# Sheet1.net
KiCad netlist of a schematic drawn in Altium Designer
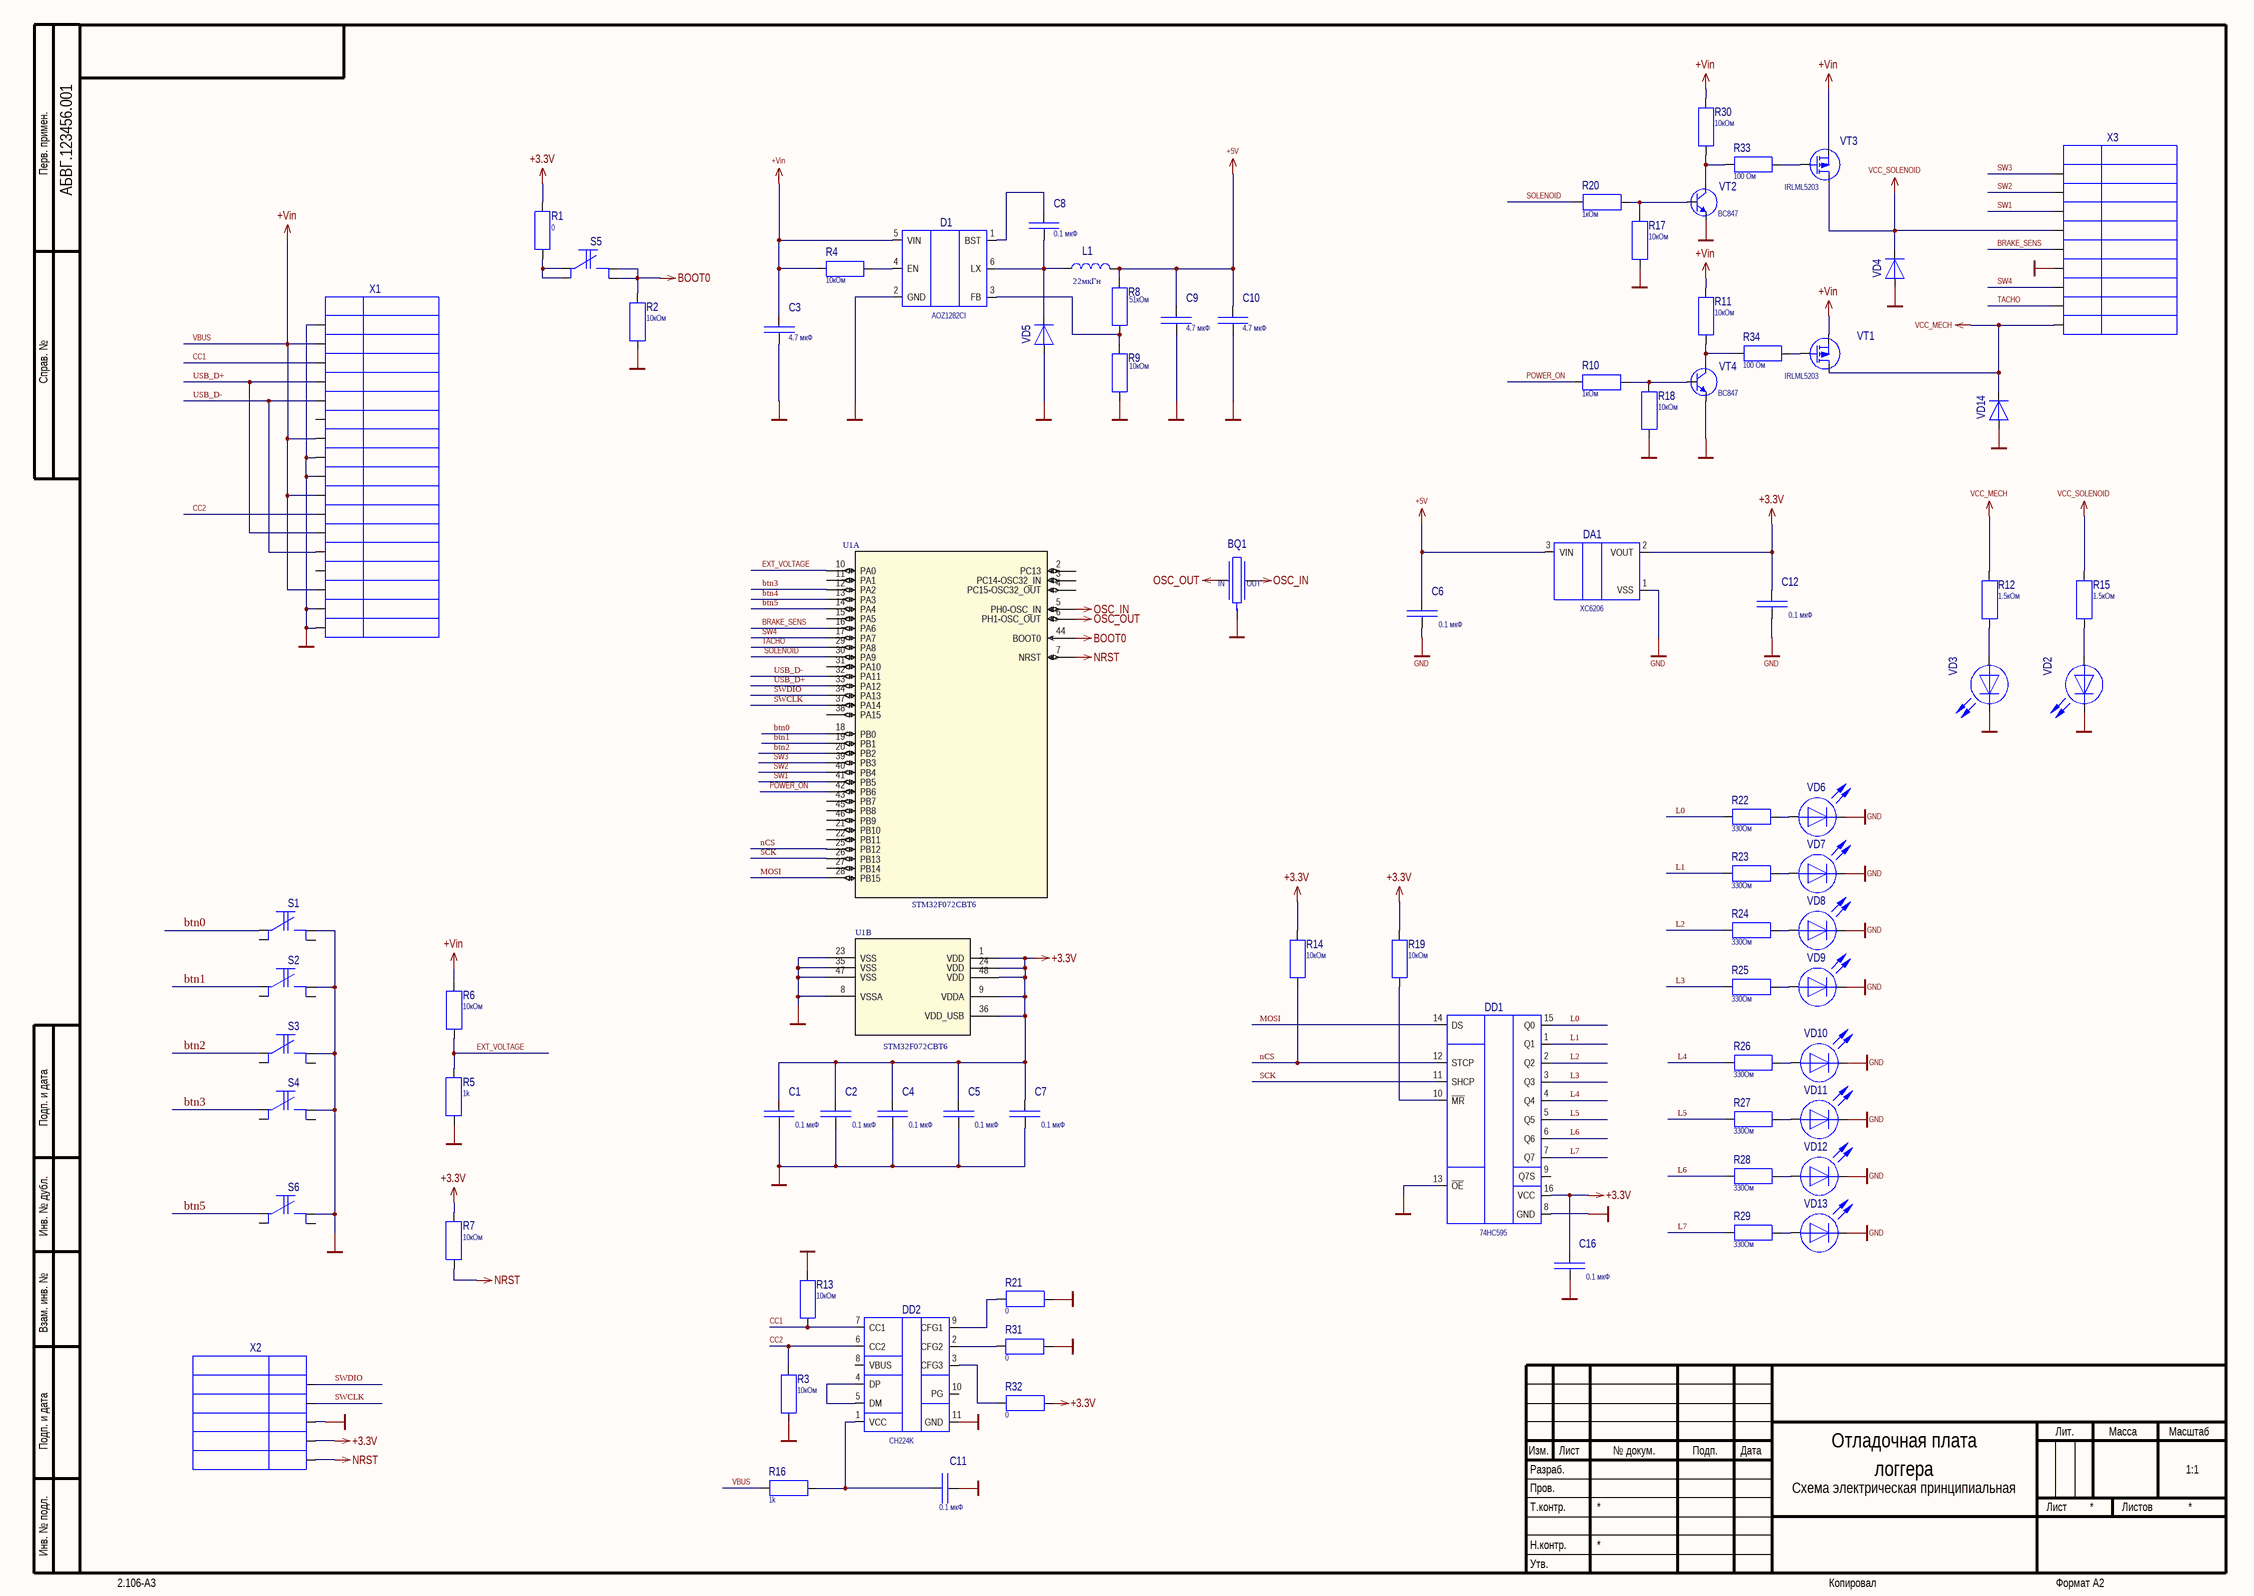
[diagram p0: Sheet1.SchDoc]

(export (version "E")
  (design (tool "Eeschema 10.0.6"))
  (components
    (comp (ref "BQ1")
      (value "CSTCE8M00G15C99")
      (footprint "CRYSTAL-SMD_3P-L3.2-W1.3-P1.2-BL-1")
      (fields (field (name "MANUFACTURER") "ф. Murata"))
      (libsource (lib "Common_lib") (part "CSTCE8M00G15C99"))
    )
    (comp (ref "C1")
      (value "0.1 мкФ")
      (footprint "C0805")
      (fields (field (name "TOLERANCE") "5%") (field (name "Comment") "C_2"))
      (libsource (lib "tsb_lib") (part "C_2"))
    )
    (comp (ref "C2")
      (value "0.1 мкФ")
      (footprint "C0805")
      (fields (field (name "TOLERANCE") "5%") (field (name "Comment") "C_2"))
      (libsource (lib "tsb_lib") (part "C_2"))
    )
    (comp (ref "C3")
      (value "4.7 мкФ")
      (footprint "C0805")
      (fields (field (name "TOLERANCE") "5%") (field (name "Comment") "C_2"))
      (libsource (lib "tsb_lib") (part "C_2"))
    )
    (comp (ref "C4")
      (value "0.1 мкФ")
      (footprint "C0805")
      (fields (field (name "TOLERANCE") "5%") (field (name "Comment") "C_2"))
      (libsource (lib "tsb_lib") (part "C_2"))
    )
    (comp (ref "C5")
      (value "0.1 мкФ")
      (footprint "C0805")
      (fields (field (name "TOLERANCE") "5%") (field (name "Comment") "C_2"))
      (libsource (lib "tsb_lib") (part "C_2"))
    )
    (comp (ref "C6")
      (value "0.1 мкФ")
      (footprint "C0805")
      (fields (field (name "TOLERANCE") "5%") (field (name "Comment") "C_2"))
      (libsource (lib "tsb_lib") (part "C_2"))
    )
    (comp (ref "C7")
      (value "0.1 мкФ")
      (footprint "C0805")
      (fields (field (name "TOLERANCE") "5%") (field (name "Comment") "C_2"))
      (libsource (lib "tsb_lib") (part "C_2"))
    )
    (comp (ref "C8")
      (value "0.1 мкФ")
      (footprint "C0805")
      (fields (field (name "TOLERANCE") "5%") (field (name "Comment") "C_2"))
      (libsource (lib "tsb_lib") (part "C_2"))
    )
    (comp (ref "C9")
      (value "4.7 мкФ")
      (footprint "C0805")
      (fields (field (name "TOLERANCE") "5%") (field (name "Comment") "C_2"))
      (libsource (lib "tsb_lib") (part "C_2"))
    )
    (comp (ref "C10")
      (value "4.7 мкФ")
      (footprint "C0805")
      (fields (field (name "TOLERANCE") "5%") (field (name "Comment") "C_2"))
      (libsource (lib "tsb_lib") (part "C_2"))
    )
    (comp (ref "C11")
      (value "0.1 мкФ")
      (footprint "C0805")
      (fields (field (name "TOLERANCE") "5%") (field (name "Comment") "C_2"))
      (libsource (lib "tsb_lib") (part "C_2"))
    )
    (comp (ref "C12")
      (value "0.1 мкФ")
      (footprint "C0805")
      (fields (field (name "TOLERANCE") "5%") (field (name "Comment") "C_2"))
      (libsource (lib "tsb_lib") (part "C_2"))
    )
    (comp (ref "C16")
      (value "0.1 мкФ")
      (footprint "C0805")
      (fields (field (name "TOLERANCE") "5%") (field (name "Comment") "C_2"))
      (libsource (lib "tsb_lib") (part "C_2"))
    )
    (comp (ref "D1")
      (value "AOZ1282CI")
      (footprint "SOT23-6_M")
      (fields (field (name "MANUFACTURER") "ф. Alpha & Omega"))
      (libsource (lib "Common_lib") (part "AOZ1282CI"))
    )
    (comp (ref "DA1")
      (value "XC6206")
      (footprint "SOT23_S")
      (fields (field (name "MANUFACTURER") "ф. Torex"))
      (libsource (lib "Common_lib") (part "XC6206"))
    )
    (comp (ref "DD1")
      (value "74HC595")
      (footprint "SO-16_M")
      (fields
        (field (name "MANUFACTURER") "ф. Nexperia B.V.")
        (field (name "MANUFACTURERPARTNUMBER") "74HC595D")
      )
      (libsource (lib "Common_lib") (part "74HC595"))
    )
    (comp (ref "DD2")
      (value "CH224K")
      (footprint "ESSOP-10_L4.9-W3.9-P1.0-LS6.0-TL-EP")
      (fields (field (name "MANUFACTURER") "ф. WCH"))
      (libsource (lib "Common_lib") (part "CH224K"))
    )
    (comp (ref "L1")
      (value "22мкГн")
      (footprint "4.5X3.0")
      (fields
        (field (name "MANUFACTURER") "ф. CODACA")
        (field (name "TOLERANCE") "10%")
        (field (name "Comment") "L_1")
      )
      (libsource (lib "Common_lib") (part "L_1"))
    )
    (comp (ref "R1")
      (value "0")
      (footprint "r0805")
      (fields (field (name "TOLERANCE") "5%") (field (name "Comment") "R_1"))
      (libsource (lib "rc_lib") (part "R_1"))
    )
    (comp (ref "R2")
      (value "10кОм")
      (footprint "r0805")
      (fields (field (name "TOLERANCE") "5%") (field (name "Comment") "R_1"))
      (libsource (lib "rc_lib") (part "R_1"))
    )
    (comp (ref "R3")
      (value "10кОм")
      (footprint "r0805")
      (fields (field (name "TOLERANCE") "5%") (field (name "Comment") "R_1"))
      (libsource (lib "rc_lib") (part "R_1"))
    )
    (comp (ref "R4")
      (value "10кОм")
      (footprint "R0805")
      (fields (field (name "TOLERANCE") "5%") (field (name "Comment") "R_1"))
      (libsource (lib "rc_lib") (part "R_1"))
    )
    (comp (ref "R5")
      (value "1k")
      (footprint "r0805")
      (fields (field (name "TOLERANCE") "5%") (field (name "Comment") "R_1"))
      (libsource (lib "rc_lib") (part "R_1"))
    )
    (comp (ref "R6")
      (value "10кОм")
      (footprint "r0805")
      (fields (field (name "TOLERANCE") "5%") (field (name "Comment") "R_1"))
      (libsource (lib "rc_lib") (part "R_1"))
    )
    (comp (ref "R7")
      (value "10кОм")
      (footprint "r0805")
      (fields (field (name "TOLERANCE") "5%") (field (name "Comment") "R_1"))
      (libsource (lib "rc_lib") (part "R_1"))
    )
    (comp (ref "R8")
      (value "51кОм")
      (footprint "R0805")
      (fields (field (name "TOLERANCE") "5%") (field (name "Comment") "R_1"))
      (libsource (lib "rc_lib") (part "R_1"))
    )
    (comp (ref "R9")
      (value "10кОм")
      (footprint "R0805")
      (fields (field (name "TOLERANCE") "5%") (field (name "Comment") "R_1"))
      (libsource (lib "rc_lib") (part "R_1"))
    )
    (comp (ref "R10")
      (value "1кОм")
      (footprint "r0805")
      (fields (field (name "TOLERANCE") "5%") (field (name "Comment") "R_1"))
      (libsource (lib "rc_lib") (part "R_1"))
    )
    (comp (ref "R11")
      (value "10кОм")
      (footprint "r0805")
      (fields (field (name "TOLERANCE") "5%") (field (name "Comment") "R_1"))
      (libsource (lib "rc_lib") (part "R_1"))
    )
    (comp (ref "R12")
      (value "1.5кОм")
      (footprint "R0805")
      (fields (field (name "TOLERANCE") "5%") (field (name "Comment") "R_1"))
      (libsource (lib "rc_lib") (part "R_1"))
    )
    (comp (ref "R13")
      (value "10кОм")
      (footprint "r0805")
      (fields (field (name "TOLERANCE") "5%") (field (name "Comment") "R_1"))
      (libsource (lib "rc_lib") (part "R_1"))
    )
    (comp (ref "R14")
      (value "10кОм")
      (footprint "r0805")
      (fields (field (name "TOLERANCE") "5%") (field (name "Comment") "R_1"))
      (libsource (lib "rc_lib") (part "R_1"))
    )
    (comp (ref "R15")
      (value "1.5кОм")
      (footprint "R0805")
      (fields (field (name "TOLERANCE") "5%") (field (name "Comment") "R_1"))
      (libsource (lib "rc_lib") (part "R_1"))
    )
    (comp (ref "R16")
      (value "1k")
      (footprint "r0805")
      (fields (field (name "TOLERANCE") "5%") (field (name "Comment") "R_1"))
      (libsource (lib "rc_lib") (part "R_1"))
    )
    (comp (ref "R17")
      (value "10кОм")
      (footprint "r0805")
      (fields (field (name "TOLERANCE") "5%") (field (name "Comment") "R_1"))
      (libsource (lib "rc_lib") (part "R_1"))
    )
    (comp (ref "R18")
      (value "10кОм")
      (footprint "r0805")
      (fields (field (name "TOLERANCE") "5%") (field (name "Comment") "R_1"))
      (libsource (lib "rc_lib") (part "R_1"))
    )
    (comp (ref "R19")
      (value "10кОм")
      (footprint "r0805")
      (fields (field (name "TOLERANCE") "5%") (field (name "Comment") "R_1"))
      (libsource (lib "rc_lib") (part "R_1"))
    )
    (comp (ref "R20")
      (value "1кОм")
      (footprint "r0805")
      (fields (field (name "TOLERANCE") "5%") (field (name "Comment") "R_1"))
      (libsource (lib "rc_lib") (part "R_1"))
    )
    (comp (ref "R21")
      (value "0")
      (footprint "r0805")
      (fields (field (name "TOLERANCE") "5%") (field (name "Comment") "R_1"))
      (libsource (lib "rc_lib") (part "R_1"))
    )
    (comp (ref "R22")
      (value "330Ом")
      (footprint "R0805")
      (fields (field (name "TOLERANCE") "5%") (field (name "Comment") "R_1"))
      (libsource (lib "rc_lib") (part "R_1"))
    )
    (comp (ref "R23")
      (value "330Ом")
      (footprint "R0805")
      (fields (field (name "TOLERANCE") "5%") (field (name "Comment") "R_1"))
      (libsource (lib "rc_lib") (part "R_1"))
    )
    (comp (ref "R24")
      (value "330Ом")
      (footprint "R0805")
      (fields (field (name "TOLERANCE") "5%") (field (name "Comment") "R_1"))
      (libsource (lib "rc_lib") (part "R_1"))
    )
    (comp (ref "R25")
      (value "330Ом")
      (footprint "R0805")
      (fields (field (name "TOLERANCE") "5%") (field (name "Comment") "R_1"))
      (libsource (lib "rc_lib") (part "R_1"))
    )
    (comp (ref "R26")
      (value "330Ом")
      (footprint "R0805")
      (fields (field (name "TOLERANCE") "5%") (field (name "Comment") "R_1"))
      (libsource (lib "rc_lib") (part "R_1"))
    )
    (comp (ref "R27")
      (value "330Ом")
      (footprint "R0805")
      (fields (field (name "TOLERANCE") "5%") (field (name "Comment") "R_1"))
      (libsource (lib "rc_lib") (part "R_1"))
    )
    (comp (ref "R28")
      (value "330Ом")
      (footprint "R0805")
      (fields (field (name "TOLERANCE") "5%") (field (name "Comment") "R_1"))
      (libsource (lib "rc_lib") (part "R_1"))
    )
    (comp (ref "R29")
      (value "330Ом")
      (footprint "R0805")
      (fields (field (name "TOLERANCE") "5%") (field (name "Comment") "R_1"))
      (libsource (lib "rc_lib") (part "R_1"))
    )
    (comp (ref "R30")
      (value "10кОм")
      (footprint "r0805")
      (fields (field (name "TOLERANCE") "5%") (field (name "Comment") "R_1"))
      (libsource (lib "rc_lib") (part "R_1"))
    )
    (comp (ref "R31")
      (value "0")
      (footprint "r0805")
      (fields (field (name "TOLERANCE") "5%") (field (name "Comment") "R_1"))
      (libsource (lib "rc_lib") (part "R_1"))
    )
    (comp (ref "R32")
      (value "0")
      (footprint "r0805")
      (fields (field (name "TOLERANCE") "5%") (field (name "Comment") "R_1"))
      (libsource (lib "rc_lib") (part "R_1"))
    )
    (comp (ref "R33")
      (value "100 Ом")
      (footprint "r0805")
      (fields (field (name "TOLERANCE") "5%") (field (name "Comment") "R_1"))
      (libsource (lib "rc_lib") (part "R_1"))
    )
    (comp (ref "R34")
      (value "100 Ом")
      (footprint "r0805")
      (fields (field (name "TOLERANCE") "5%") (field (name "Comment") "R_1"))
      (libsource (lib "rc_lib") (part "R_1"))
    )
    (comp (ref "S1")
      (value "SW_BOT")
      (footprint "SW-PB")
      (fields (field (name "MANUFACTURERPARTNUMBER") "Кнопка тактовая 4.5x6.5мм"))
      (libsource (lib "Common_lib") (part "SW_BOT"))
    )
    (comp (ref "S2")
      (value "SW_BOT")
      (footprint "SW-PB")
      (fields (field (name "MANUFACTURERPARTNUMBER") "Кнопка тактовая 4.5x6.5мм"))
      (libsource (lib "Common_lib") (part "SW_BOT"))
    )
    (comp (ref "S3")
      (value "SW_BOT")
      (footprint "SW-PB")
      (fields (field (name "MANUFACTURERPARTNUMBER") "Кнопка тактовая 4.5x6.5мм"))
      (libsource (lib "Common_lib") (part "SW_BOT"))
    )
    (comp (ref "S4")
      (value "SW_BOT")
      (footprint "SW-PB")
      (fields (field (name "MANUFACTURERPARTNUMBER") "Кнопка тактовая 4.5x6.5мм"))
      (libsource (lib "Common_lib") (part "SW_BOT"))
    )
    (comp (ref "S5")
      (value "SW_BOT")
      (footprint "SW-PB")
      (fields (field (name "MANUFACTURERPARTNUMBER") "Кнопка тактовая 4.5x6.5мм"))
      (libsource (lib "Common_lib") (part "SW_BOT"))
    )
    (comp (ref "S6")
      (value "SW_BOT")
      (footprint "SW-PB")
      (fields (field (name "MANUFACTURERPARTNUMBER") "Кнопка тактовая 4.5x6.5мм"))
      (libsource (lib "Common_lib") (part "SW_BOT"))
    )
    (comp (ref "U1")
      (value "STM32F072CBT6")
      (footprint "TQFP48_M")
      (description "No Description Available")
      (fields
        (field (name "MANUFACTURER_PART_NUMBER") "stm32l052cl3")
        (field (name "COPYRIGHT") "Copyright (C) 2016 Accelerated Designs. All rights reserved")
      )
      (libsource (lib "2019-10-06_14-30-46") (part "STM32L052CL3"))
    )
    (comp (ref "VD2")
      (value "LED")
      (footprint "L0805")
      (fields (field (name "MANUFACTURERPARTNUMBER") "KPT-2012SGC (Красный)  *любой 0805"))
      (libsource (lib "rc_lib") (part "LED"))
    )
    (comp (ref "VD3")
      (value "LED")
      (footprint "L0805")
      (fields (field (name "MANUFACTURERPARTNUMBER") "KPT-2012SGC (Красный)  *любой 0805"))
      (libsource (lib "rc_lib") (part "LED"))
    )
    (comp (ref "VD4")
      (value "MBR0540T1G")
      (footprint "SOD123")
      (fields (field (name "MANUFACTURER") "ф.  ON Semi"))
      (libsource (lib "log_lib") (part "MBR0540T1G"))
    )
    (comp (ref "VD5")
      (value "MBR0540T1G")
      (footprint "SOD123")
      (fields (field (name "MANUFACTURER") "ф.  ON Semi"))
      (libsource (lib "log_lib") (part "MBR0540T1G"))
    )
    (comp (ref "VD6")
      (value "LED")
      (footprint "L0805")
      (fields (field (name "MANUFACTURERPARTNUMBER") "KPT-2012SGC (Зеленый)  *любой 0805"))
      (libsource (lib "rc_lib") (part "LED"))
    )
    (comp (ref "VD7")
      (value "LED")
      (footprint "L0805")
      (fields (field (name "MANUFACTURERPARTNUMBER") "KPT-2012SGC (Зеленый)  *любой 0805"))
      (libsource (lib "rc_lib") (part "LED"))
    )
    (comp (ref "VD8")
      (value "LED")
      (footprint "L0805")
      (fields (field (name "MANUFACTURERPARTNUMBER") "KPT-2012SGC (Зеленый)  *любой 0805"))
      (libsource (lib "rc_lib") (part "LED"))
    )
    (comp (ref "VD9")
      (value "LED")
      (footprint "L0805")
      (fields (field (name "MANUFACTURERPARTNUMBER") "KPT-2012SGC (Зеленый)  *любой 0805"))
      (libsource (lib "rc_lib") (part "LED"))
    )
    (comp (ref "VD10")
      (value "LED")
      (footprint "L0805")
      (fields (field (name "MANUFACTURERPARTNUMBER") "KPT-2012SGC (Зеленый)  *любой 0805"))
      (libsource (lib "rc_lib") (part "LED"))
    )
    (comp (ref "VD11")
      (value "LED")
      (footprint "L0805")
      (fields (field (name "MANUFACTURERPARTNUMBER") "KPT-2012SGC (Зеленый)  *любой 0805"))
      (libsource (lib "rc_lib") (part "LED"))
    )
    (comp (ref "VD12")
      (value "LED")
      (footprint "L0805")
      (fields (field (name "MANUFACTURERPARTNUMBER") "KPT-2012SGC (Зеленый)  *любой 0805"))
      (libsource (lib "rc_lib") (part "LED"))
    )
    (comp (ref "VD13")
      (value "LED")
      (footprint "L0805")
      (fields (field (name "MANUFACTURERPARTNUMBER") "KPT-2012SGC (Зеленый)  *любой 0805"))
      (libsource (lib "rc_lib") (part "LED"))
    )
    (comp (ref "VD14")
      (value "MBR0540T1G")
      (footprint "SOD123")
      (fields (field (name "MANUFACTURER") "ф.  ON Semi"))
      (libsource (lib "log_lib") (part "MBR0540T1G"))
    )
    (comp (ref "VT1")
      (value "IRLML5203")
      (footprint "SOT23_M")
      (fields (field (name "MANUFACTURER") "ф. IR"))
      (libsource (lib "Common_lib") (part "IRLML5203"))
    )
    (comp (ref "VT2")
      (value "BC847")
      (footprint "SOT23_S")
      (fields (field (name "MANUFACTURER") "ф. NXP"))
      (libsource (lib "Common_lib") (part "BC847"))
    )
    (comp (ref "VT3")
      (value "IRLML5203")
      (footprint "SOT23_M")
      (fields (field (name "MANUFACTURER") "ф. IR"))
      (libsource (lib "Common_lib") (part "IRLML5203"))
    )
    (comp (ref "VT4")
      (value "BC847")
      (footprint "SOT23_S")
      (fields (field (name "MANUFACTURER") "ф. NXP"))
      (libsource (lib "Common_lib") (part "BC847"))
    )
    (comp (ref "X1")
      (value "USBC-16PIN-VERTICAL")
      (footprint "USB-C-16-pin-vertical")
      (fields
        (field (name "MANUFACTURER") "ф. Ningbo Zhenqin Electronic")
        (field (name "MANUFACTURERPARTNUMBER") "PLS11")
      )
      (libsource (lib "Common_lib") (part "USBC-16PIN-VERTICAL"))
    )
    (comp (ref "X2")
      (value "PLS5")
      (footprint "HDR1X5")
      (fields (field (name "MANUFACTURER") "ф. Ningbo Zhenqin Electronic"))
      (libsource (lib "Common_lib") (part "PLS5"))
    )
    (comp (ref "X3")
      (value "PLS9")
      (footprint "PH-9A_P")
      (fields
        (field (name "MANUFACTURER") "ф. Ningbo Zhenqin Electronic")
        (field (name "MANUFACTURERPARTNUMBER") "PH2.0-9A_P")
      )
      (libsource (lib "Common_lib") (part "PLS9"))
    )
  )
  (nets
    (net (code "1") (name "+3.3V") (class "Default")
      (node (ref "C1") (pin "1") (pintype "passive"))
      (node (ref "C12") (pin "1") (pintype "passive"))
      (node (ref "C16") (pin "1") (pintype "passive"))
      (node (ref "C2") (pin "1") (pintype "passive"))
      (node (ref "C4") (pin "1") (pintype "passive"))
      (node (ref "C5") (pin "1") (pintype "passive"))
      (node (ref "C7") (pin "1") (pintype "passive"))
      (node (ref "DA1") (pin "2") (pinfunction "VOUT_2") (pintype "passive"))
      (node (ref "DD1") (pin "16") (pinfunction "VCC_16") (pintype "passive"))
      (node (ref "R1") (pin "2") (pintype "passive"))
      (node (ref "R14") (pin "1") (pintype "passive"))
      (node (ref "R19") (pin "1") (pintype "passive"))
      (node (ref "R32") (pin "1") (pintype "passive"))
      (node (ref "R7") (pin "2") (pintype "passive"))
      (node (ref "U1") (pin "1") (pinfunction "VDD_1") (pintype "power_in"))
      (node (ref "U1") (pin "24") (pinfunction "VDD_24") (pintype "power_in"))
      (node (ref "U1") (pin "36") (pinfunction "VDD_USB_36") (pintype "power_in"))
      (node (ref "U1") (pin "48") (pinfunction "VDD_48") (pintype "power_in"))
      (node (ref "U1") (pin "9") (pinfunction "VDDA_9") (pintype "power_in"))
      (node (ref "X2") (pin "4") (pintype "passive"))
    )
    (net (code "2") (name "+5V") (class "Default")
      (node (ref "C10") (pin "1") (pintype "passive"))
      (node (ref "C6") (pin "1") (pintype "passive"))
      (node (ref "C9") (pin "1") (pintype "passive"))
      (node (ref "DA1") (pin "3") (pinfunction "VIN_3") (pintype "passive"))
      (node (ref "L1") (pin "2") (pintype "passive"))
      (node (ref "R8") (pin "1") (pintype "passive"))
    )
    (net (code "3") (name "+Vin") (class "Default")
      (node (ref "C3") (pin "1") (pintype "passive"))
      (node (ref "D1") (pin "5") (pinfunction "VIN_5") (pintype "passive"))
      (node (ref "R11") (pin "1") (pintype "passive"))
      (node (ref "R16") (pin "2") (pintype "passive"))
      (node (ref "R30") (pin "1") (pintype "passive"))
      (node (ref "R4") (pin "1") (pintype "passive"))
      (node (ref "R6") (pin "1") (pintype "passive"))
      (node (ref "VT1") (pin "2") (pinfunction "S_2") (pintype "passive"))
      (node (ref "VT3") (pin "2") (pinfunction "S_2") (pintype "passive"))
      (node (ref "X1") (pin "A4") (pintype "passive"))
      (node (ref "X1") (pin "A9") (pintype "passive"))
      (node (ref "X1") (pin "B4") (pintype "passive"))
      (node (ref "X1") (pin "B9") (pintype "passive"))
    )
    (net (code "4") (name "/BRAKE_SENS") (class "Default")
      (node (ref "U1") (pin "16") (pinfunction "PA6_16") (pintype "bidirectional"))
      (node (ref "X3") (pin "5") (pintype "passive"))
    )
    (net (code "5") (name "/CC1") (class "Default")
      (node (ref "DD2") (pin "7") (pinfunction "CC1_7") (pintype "passive"))
      (node (ref "R13") (pin "2") (pintype "passive"))
      (node (ref "X1") (pin "A5") (pintype "passive"))
    )
    (net (code "6") (name "/CC2") (class "Default")
      (node (ref "DD2") (pin "6") (pinfunction "CC2_6") (pintype "passive"))
      (node (ref "R3") (pin "1") (pintype "passive"))
      (node (ref "X1") (pin "B5") (pintype "passive"))
    )
    (net (code "7") (name "/EXT_VOLTAGE") (class "Default")
      (node (ref "R5") (pin "2") (pintype "passive"))
      (node (ref "R6") (pin "2") (pintype "passive"))
      (node (ref "U1") (pin "10") (pinfunction "PA0_10") (pintype "bidirectional"))
    )
    (net (code "8") (name "/L0") (class "Default")
      (node (ref "DD1") (pin "15") (pinfunction "Q0_15") (pintype "passive"))
      (node (ref "R22") (pin "2") (pintype "passive"))
    )
    (net (code "9") (name "/L1") (class "Default")
      (node (ref "DD1") (pin "1") (pinfunction "Q1_1") (pintype "passive"))
      (node (ref "R23") (pin "2") (pintype "passive"))
    )
    (net (code "10") (name "/L2") (class "Default")
      (node (ref "DD1") (pin "2") (pinfunction "Q2_2") (pintype "passive"))
      (node (ref "R24") (pin "2") (pintype "passive"))
    )
    (net (code "11") (name "/L3") (class "Default")
      (node (ref "DD1") (pin "3") (pinfunction "Q3_3") (pintype "passive"))
      (node (ref "R25") (pin "2") (pintype "passive"))
    )
    (net (code "12") (name "/L4") (class "Default")
      (node (ref "DD1") (pin "4") (pinfunction "Q4_4") (pintype "passive"))
      (node (ref "R26") (pin "2") (pintype "passive"))
    )
    (net (code "13") (name "/L5") (class "Default")
      (node (ref "DD1") (pin "5") (pinfunction "Q5_5") (pintype "passive"))
      (node (ref "R27") (pin "2") (pintype "passive"))
    )
    (net (code "14") (name "/L6") (class "Default")
      (node (ref "DD1") (pin "6") (pinfunction "Q6_6") (pintype "passive"))
      (node (ref "R28") (pin "2") (pintype "passive"))
    )
    (net (code "15") (name "/L7") (class "Default")
      (node (ref "DD1") (pin "7") (pinfunction "Q7_7") (pintype "passive"))
      (node (ref "R29") (pin "2") (pintype "passive"))
    )
    (net (code "16") (name "/MOSI") (class "Default")
      (node (ref "DD1") (pin "14") (pinfunction "DS_14") (pintype "passive"))
      (node (ref "U1") (pin "28") (pinfunction "PB15_28") (pintype "bidirectional"))
    )
    (net (code "17") (name "/POWER_ON") (class "Default")
      (node (ref "R10") (pin "1") (pintype "passive"))
      (node (ref "U1") (pin "42") (pinfunction "PB6_42") (pintype "bidirectional"))
    )
    (net (code "18") (name "/SCK") (class "Default")
      (node (ref "DD1") (pin "11") (pinfunction "SHCP_11") (pintype "passive"))
      (node (ref "U1") (pin "26") (pinfunction "PB13_26") (pintype "bidirectional"))
    )
    (net (code "19") (name "/SOLENOID") (class "Default")
      (node (ref "R20") (pin "2") (pintype "passive"))
      (node (ref "U1") (pin "30") (pinfunction "PA9_30") (pintype "bidirectional"))
    )
    (net (code "20") (name "/SW1") (class "Default")
      (node (ref "U1") (pin "41") (pinfunction "PB5_41") (pintype "bidirectional"))
      (node (ref "X3") (pin "3") (pintype "passive"))
    )
    (net (code "21") (name "/SW2") (class "Default")
      (node (ref "U1") (pin "40") (pinfunction "PB4_40") (pintype "bidirectional"))
      (node (ref "X3") (pin "2") (pintype "passive"))
    )
    (net (code "22") (name "/SW3") (class "Default")
      (node (ref "U1") (pin "39") (pinfunction "PB3_39") (pintype "bidirectional"))
      (node (ref "X3") (pin "1") (pintype "passive"))
    )
    (net (code "23") (name "/SW4") (class "Default")
      (node (ref "U1") (pin "17") (pinfunction "PA7_17") (pintype "bidirectional"))
      (node (ref "X3") (pin "7") (pintype "passive"))
    )
    (net (code "24") (name "/SWCLK") (class "Default")
      (node (ref "U1") (pin "37") (pinfunction "PA14_37") (pintype "bidirectional"))
      (node (ref "X2") (pin "2") (pintype "passive"))
    )
    (net (code "25") (name "/SWDIO") (class "Default")
      (node (ref "U1") (pin "34") (pinfunction "PA13_34") (pintype "bidirectional"))
      (node (ref "X2") (pin "1") (pintype "passive"))
    )
    (net (code "26") (name "/TACHO") (class "Default")
      (node (ref "U1") (pin "29") (pinfunction "PA8_29") (pintype "bidirectional"))
      (node (ref "X3") (pin "8") (pintype "passive"))
    )
    (net (code "27") (name "/USB_D+") (class "Default")
      (node (ref "U1") (pin "33") (pinfunction "PA12_33") (pintype "bidirectional"))
      (node (ref "X1") (pin "A6") (pintype "passive"))
      (node (ref "X1") (pin "B6") (pintype "passive"))
    )
    (net (code "28") (name "/USB_D-") (class "Default")
      (node (ref "U1") (pin "32") (pinfunction "PA11_32") (pintype "bidirectional"))
      (node (ref "X1") (pin "A7") (pintype "passive"))
      (node (ref "X1") (pin "B7") (pintype "passive"))
    )
    (net (code "29") (name "/btn0") (class "Default")
      (node (ref "S1") (pin "1") (pintype "passive"))
      (node (ref "U1") (pin "18") (pinfunction "PB0_18") (pintype "bidirectional"))
    )
    (net (code "30") (name "/btn1") (class "Default")
      (node (ref "S2") (pin "1") (pintype "passive"))
      (node (ref "U1") (pin "19") (pinfunction "PB1_19") (pintype "bidirectional"))
    )
    (net (code "31") (name "/btn2") (class "Default")
      (node (ref "S3") (pin "1") (pintype "passive"))
      (node (ref "U1") (pin "20") (pinfunction "PB2_20") (pintype "bidirectional"))
    )
    (net (code "32") (name "/btn3") (class "Default")
      (node (ref "S4") (pin "1") (pintype "passive"))
      (node (ref "U1") (pin "12") (pinfunction "PA2_12") (pintype "bidirectional"))
    )
    (net (code "33") (name "/btn4") (class "Default")
      (node (ref "U1") (pin "13") (pinfunction "PA3_13") (pintype "bidirectional"))
    )
    (net (code "34") (name "/btn5") (class "Default")
      (node (ref "S6") (pin "1") (pintype "passive"))
      (node (ref "U1") (pin "14") (pinfunction "PA4_14") (pintype "bidirectional"))
    )
    (net (code "35") (name "/nCS") (class "Default")
      (node (ref "DD1") (pin "12") (pinfunction "STCP_12") (pintype "passive"))
      (node (ref "R14") (pin "2") (pintype "passive"))
      (node (ref "U1") (pin "25") (pinfunction "PB12_25") (pintype "bidirectional"))
    )
    (net (code "36") (name "BOOT0") (class "Default")
      (node (ref "R2") (pin "1") (pintype "passive"))
      (node (ref "S5") (pin "2") (pintype "passive"))
      (node (ref "S5") (pin "3") (pintype "passive"))
      (node (ref "U1") (pin "44") (pinfunction "BOOT0_44") (pintype "input"))
    )
    (net (code "37") (name "GND") (class "Default")
      (node (ref "BQ1") (pin "2") (pintype "passive"))
      (node (ref "C1") (pin "2") (pintype "passive"))
      (node (ref "C10") (pin "2") (pintype "passive"))
      (node (ref "C11") (pin "2") (pintype "passive"))
      (node (ref "C12") (pin "2") (pintype "passive"))
      (node (ref "C16") (pin "2") (pintype "passive"))
      (node (ref "C2") (pin "2") (pintype "passive"))
      (node (ref "C3") (pin "2") (pintype "passive"))
      (node (ref "C4") (pin "2") (pintype "passive"))
      (node (ref "C5") (pin "2") (pintype "passive"))
      (node (ref "C6") (pin "2") (pintype "passive"))
      (node (ref "C7") (pin "2") (pintype "passive"))
      (node (ref "C9") (pin "2") (pintype "passive"))
      (node (ref "D1") (pin "2") (pinfunction "GND_2") (pintype "passive"))
      (node (ref "DA1") (pin "1") (pinfunction "VSS_1") (pintype "passive"))
      (node (ref "DD1") (pin "13") (pinfunction "OE_13") (pintype "passive"))
      (node (ref "DD1") (pin "8") (pinfunction "GND_8") (pintype "passive"))
      (node (ref "DD2") (pin "11") (pinfunction "GND_11") (pintype "passive"))
      (node (ref "R13") (pin "1") (pintype "passive"))
      (node (ref "R17") (pin "2") (pintype "passive"))
      (node (ref "R18") (pin "2") (pintype "passive"))
      (node (ref "R2") (pin "2") (pintype "passive"))
      (node (ref "R21") (pin "1") (pintype "passive"))
      (node (ref "R3") (pin "2") (pintype "passive"))
      (node (ref "R31") (pin "2") (pintype "passive"))
      (node (ref "R5") (pin "1") (pintype "passive"))
      (node (ref "R9") (pin "2") (pintype "passive"))
      (node (ref "S1") (pin "2") (pintype "passive"))
      (node (ref "S2") (pin "2") (pintype "passive"))
      (node (ref "S3") (pin "2") (pintype "passive"))
      (node (ref "S4") (pin "2") (pintype "passive"))
      (node (ref "S6") (pin "2") (pintype "passive"))
      (node (ref "U1") (pin "23") (pinfunction "VSS_23") (pintype "power_in"))
      (node (ref "U1") (pin "35") (pinfunction "VSS_35") (pintype "power_in"))
      (node (ref "U1") (pin "47") (pinfunction "VSS_47") (pintype "power_in"))
      (node (ref "U1") (pin "8") (pinfunction "VSSA_8") (pintype "power_in"))
      (node (ref "VD10") (pin "2") (pintype "passive"))
      (node (ref "VD11") (pin "2") (pintype "passive"))
      (node (ref "VD12") (pin "2") (pintype "passive"))
      (node (ref "VD13") (pin "2") (pintype "passive"))
      (node (ref "VD14") (pin "1") (pintype "passive"))
      (node (ref "VD2") (pin "2") (pintype "passive"))
      (node (ref "VD3") (pin "2") (pintype "passive"))
      (node (ref "VD4") (pin "1") (pintype "passive"))
      (node (ref "VD5") (pin "1") (pintype "passive"))
      (node (ref "VD6") (pin "2") (pintype "passive"))
      (node (ref "VD7") (pin "2") (pintype "passive"))
      (node (ref "VD8") (pin "2") (pintype "passive"))
      (node (ref "VD9") (pin "2") (pintype "passive"))
      (node (ref "VT2") (pin "2") (pinfunction "E_2") (pintype "passive"))
      (node (ref "VT4") (pin "2") (pinfunction "E_2") (pintype "passive"))
      (node (ref "X1") (pin "1") (pintype "passive"))
      (node (ref "X1") (pin "A1") (pintype "passive"))
      (node (ref "X1") (pin "A12") (pintype "passive"))
      (node (ref "X1") (pin "B1") (pintype "passive"))
      (node (ref "X1") (pin "B12") (pintype "passive"))
      (node (ref "X2") (pin "3") (pintype "passive"))
      (node (ref "X3") (pin "6") (pintype "passive"))
    )
    (net (code "38") (name "NRST") (class "Default")
      (node (ref "R7") (pin "1") (pintype "passive"))
      (node (ref "U1") (pin "7") (pinfunction "NRST_7") (pintype "bidirectional"))
      (node (ref "X2") (pin "5") (pintype "passive"))
    )
    (net (code "39") (name "Net-(D1-BST)") (class "Default")
      (node (ref "C8") (pin "1") (pintype "passive"))
      (node (ref "D1") (pin "1") (pinfunction "BST_1") (pintype "passive"))
    )
    (net (code "40") (name "Net-(D1-EN)") (class "Default")
      (node (ref "D1") (pin "4") (pinfunction "EN_4") (pintype "passive"))
      (node (ref "R4") (pin "2") (pintype "passive"))
    )
    (net (code "41") (name "Net-(D1-FB)") (class "Default")
      (node (ref "D1") (pin "3") (pinfunction "FB_3") (pintype "passive"))
      (node (ref "R8") (pin "2") (pintype "passive"))
      (node (ref "R9") (pin "1") (pintype "passive"))
    )
    (net (code "42") (name "Net-(D1-LX)") (class "Default")
      (node (ref "C8") (pin "2") (pintype "passive"))
      (node (ref "D1") (pin "6") (pinfunction "LX_6") (pintype "passive"))
      (node (ref "L1") (pin "1") (pintype "passive"))
      (node (ref "VD5") (pin "2") (pintype "passive"))
    )
    (net (code "43") (name "Net-(DD1-MR)") (class "Default")
      (node (ref "DD1") (pin "10") (pinfunction "MR_10") (pintype "passive"))
      (node (ref "R19") (pin "2") (pintype "passive"))
    )
    (net (code "44") (name "Net-(DD2-CFG1)") (class "Default")
      (node (ref "DD2") (pin "9") (pinfunction "CFG1_9") (pintype "passive"))
      (node (ref "R21") (pin "2") (pintype "passive"))
    )
    (net (code "45") (name "Net-(DD2-CFG2)") (class "Default")
      (node (ref "DD2") (pin "2") (pinfunction "CFG2_2") (pintype "passive"))
      (node (ref "R31") (pin "1") (pintype "passive"))
    )
    (net (code "46") (name "Net-(DD2-CFG3)") (class "Default")
      (node (ref "DD2") (pin "3") (pinfunction "CFG3_3") (pintype "passive"))
      (node (ref "R32") (pin "2") (pintype "passive"))
    )
    (net (code "47") (name "Net-(DD2-DM)") (class "Default")
      (node (ref "DD2") (pin "4") (pinfunction "DP_4") (pintype "passive"))
      (node (ref "DD2") (pin "5") (pinfunction "DM_5") (pintype "passive"))
    )
    (net (code "48") (name "Net-(DD2-VCC)") (class "Default")
      (node (ref "C11") (pin "1") (pintype "passive"))
      (node (ref "DD2") (pin "1") (pinfunction "VCC_1") (pintype "passive"))
      (node (ref "R16") (pin "1") (pintype "passive"))
    )
    (net (code "49") (name "Net-(R1-Pad1)") (class "Default")
      (node (ref "R1") (pin "1") (pintype "passive"))
      (node (ref "S5") (pin "1") (pintype "passive"))
      (node (ref "S5") (pin "4") (pintype "passive"))
    )
    (net (code "50") (name "Net-(R12-Pad2)") (class "Default")
      (node (ref "R12") (pin "2") (pintype "passive"))
      (node (ref "VD3") (pin "1") (pintype "passive"))
    )
    (net (code "51") (name "Net-(R15-Pad2)") (class "Default")
      (node (ref "R15") (pin "2") (pintype "passive"))
      (node (ref "VD2") (pin "1") (pintype "passive"))
    )
    (net (code "52") (name "Net-(R22-Pad1)") (class "Default")
      (node (ref "R22") (pin "1") (pintype "passive"))
      (node (ref "VD6") (pin "1") (pintype "passive"))
    )
    (net (code "53") (name "Net-(R23-Pad1)") (class "Default")
      (node (ref "R23") (pin "1") (pintype "passive"))
      (node (ref "VD7") (pin "1") (pintype "passive"))
    )
    (net (code "54") (name "Net-(R24-Pad1)") (class "Default")
      (node (ref "R24") (pin "1") (pintype "passive"))
      (node (ref "VD8") (pin "1") (pintype "passive"))
    )
    (net (code "55") (name "Net-(R25-Pad1)") (class "Default")
      (node (ref "R25") (pin "1") (pintype "passive"))
      (node (ref "VD9") (pin "1") (pintype "passive"))
    )
    (net (code "56") (name "Net-(R26-Pad1)") (class "Default")
      (node (ref "R26") (pin "1") (pintype "passive"))
      (node (ref "VD10") (pin "1") (pintype "passive"))
    )
    (net (code "57") (name "Net-(R27-Pad1)") (class "Default")
      (node (ref "R27") (pin "1") (pintype "passive"))
      (node (ref "VD11") (pin "1") (pintype "passive"))
    )
    (net (code "58") (name "Net-(R28-Pad1)") (class "Default")
      (node (ref "R28") (pin "1") (pintype "passive"))
      (node (ref "VD12") (pin "1") (pintype "passive"))
    )
    (net (code "59") (name "Net-(R29-Pad1)") (class "Default")
      (node (ref "R29") (pin "1") (pintype "passive"))
      (node (ref "VD13") (pin "1") (pintype "passive"))
    )
    (net (code "60") (name "Net-(VT1-G)") (class "Default")
      (node (ref "R34") (pin "1") (pintype "passive"))
      (node (ref "VT1") (pin "1") (pinfunction "G_1") (pintype "passive"))
    )
    (net (code "61") (name "Net-(VT2-B)") (class "Default")
      (node (ref "R17") (pin "1") (pintype "passive"))
      (node (ref "R20") (pin "1") (pintype "passive"))
      (node (ref "VT2") (pin "1") (pinfunction "B_1") (pintype "passive"))
    )
    (net (code "62") (name "Net-(VT2-C)") (class "Default")
      (node (ref "R30") (pin "2") (pintype "passive"))
      (node (ref "R33") (pin "2") (pintype "passive"))
      (node (ref "VT2") (pin "3") (pinfunction "C_3") (pintype "passive"))
    )
    (net (code "63") (name "Net-(VT3-G)") (class "Default")
      (node (ref "R33") (pin "1") (pintype "passive"))
      (node (ref "VT3") (pin "1") (pinfunction "G_1") (pintype "passive"))
    )
    (net (code "64") (name "Net-(VT4-B)") (class "Default")
      (node (ref "R10") (pin "2") (pintype "passive"))
      (node (ref "R18") (pin "1") (pintype "passive"))
      (node (ref "VT4") (pin "1") (pinfunction "B_1") (pintype "passive"))
    )
    (net (code "65") (name "Net-(VT4-C)") (class "Default")
      (node (ref "R11") (pin "2") (pintype "passive"))
      (node (ref "R34") (pin "2") (pintype "passive"))
      (node (ref "VT4") (pin "3") (pinfunction "C_3") (pintype "passive"))
    )
    (net (code "66") (name "OSC_IN") (class "Default")
      (node (ref "BQ1") (pin "3") (pintype "passive"))
      (node (ref "U1") (pin "5") (pinfunction "PH0-OSC_IN_5") (pintype "bidirectional"))
    )
    (net (code "67") (name "OSC_OUT") (class "Default")
      (node (ref "BQ1") (pin "1") (pintype "passive"))
      (node (ref "U1") (pin "6") (pinfunction "PH1-OSC_OUT_6") (pintype "bidirectional"))
    )
    (net (code "68") (name "VCC_MECH") (class "Default")
      (node (ref "R12") (pin "1") (pintype "passive"))
      (node (ref "VD14") (pin "2") (pintype "passive"))
      (node (ref "VT1") (pin "3") (pinfunction "D_3") (pintype "passive"))
      (node (ref "X3") (pin "9") (pintype "passive"))
    )
    (net (code "69") (name "VCC_SOLENOID") (class "Default")
      (node (ref "R15") (pin "1") (pintype "passive"))
      (node (ref "VD4") (pin "2") (pintype "passive"))
      (node (ref "VT3") (pin "3") (pinfunction "D_3") (pintype "passive"))
      (node (ref "X3") (pin "4") (pintype "passive"))
    )
    (net (code "70") (name "unconnected-(DD1-Q7S-Pad9)") (class "Default")
      (node (ref "DD1") (pin "9") (pinfunction "Q7S_9") (pintype "passive"))
    )
    (net (code "71") (name "unconnected-(DD2-PG-Pad10)") (class "Default")
      (node (ref "DD2") (pin "10") (pinfunction "PG_10") (pintype "passive"))
    )
    (net (code "72") (name "unconnected-(DD2-VBUS-Pad8)") (class "Default")
      (node (ref "DD2") (pin "8") (pinfunction "VBUS_8") (pintype "passive"))
    )
    (net (code "73") (name "unconnected-(S1-Pad3)") (class "Default")
      (node (ref "S1") (pin "3") (pintype "passive"))
    )
    (net (code "74") (name "unconnected-(S1-Pad4)") (class "Default")
      (node (ref "S1") (pin "4") (pintype "passive"))
    )
    (net (code "75") (name "unconnected-(S2-Pad3)") (class "Default")
      (node (ref "S2") (pin "3") (pintype "passive"))
    )
    (net (code "76") (name "unconnected-(S2-Pad4)") (class "Default")
      (node (ref "S2") (pin "4") (pintype "passive"))
    )
    (net (code "77") (name "unconnected-(S3-Pad3)") (class "Default")
      (node (ref "S3") (pin "3") (pintype "passive"))
    )
    (net (code "78") (name "unconnected-(S3-Pad4)") (class "Default")
      (node (ref "S3") (pin "4") (pintype "passive"))
    )
    (net (code "79") (name "unconnected-(S4-Pad3)") (class "Default")
      (node (ref "S4") (pin "3") (pintype "passive"))
    )
    (net (code "80") (name "unconnected-(S4-Pad4)") (class "Default")
      (node (ref "S4") (pin "4") (pintype "passive"))
    )
    (net (code "81") (name "unconnected-(S6-Pad3)") (class "Default")
      (node (ref "S6") (pin "3") (pintype "passive"))
    )
    (net (code "82") (name "unconnected-(S6-Pad4)") (class "Default")
      (node (ref "S6") (pin "4") (pintype "passive"))
    )
    (net (code "83") (name "unconnected-(U1A-PA1-Pad11)") (class "Default")
      (node (ref "U1") (pin "11") (pinfunction "PA1_11") (pintype "bidirectional"))
    )
    (net (code "84") (name "unconnected-(U1A-PA5-Pad15)") (class "Default")
      (node (ref "U1") (pin "15") (pinfunction "PA5_15") (pintype "bidirectional"))
    )
    (net (code "85") (name "unconnected-(U1A-PA10-Pad31)") (class "Default")
      (node (ref "U1") (pin "31") (pinfunction "PA10_31") (pintype "bidirectional"))
    )
    (net (code "86") (name "unconnected-(U1A-PA15-Pad38)") (class "Default")
      (node (ref "U1") (pin "38") (pinfunction "PA15_38") (pintype "bidirectional"))
    )
    (net (code "87") (name "unconnected-(U1A-PB7-Pad43)") (class "Default")
      (node (ref "U1") (pin "43") (pinfunction "PB7_43") (pintype "bidirectional"))
    )
    (net (code "88") (name "unconnected-(U1A-PB8-Pad45)") (class "Default")
      (node (ref "U1") (pin "45") (pinfunction "PB8_45") (pintype "bidirectional"))
    )
    (net (code "89") (name "unconnected-(U1A-PB9-Pad46)") (class "Default")
      (node (ref "U1") (pin "46") (pinfunction "PB9_46") (pintype "bidirectional"))
    )
    (net (code "90") (name "unconnected-(U1A-PB10-Pad21)") (class "Default")
      (node (ref "U1") (pin "21") (pinfunction "PB10_21") (pintype "bidirectional"))
    )
    (net (code "91") (name "unconnected-(U1A-PB11-Pad22)") (class "Default")
      (node (ref "U1") (pin "22") (pinfunction "PB11_22") (pintype "bidirectional"))
    )
    (net (code "92") (name "unconnected-(U1A-PB14-Pad27)") (class "Default")
      (node (ref "U1") (pin "27") (pinfunction "PB14_27") (pintype "bidirectional"))
    )
    (net (code "93") (name "unconnected-(U1A-PC13-Pad2)") (class "Default")
      (node (ref "U1") (pin "2") (pinfunction "PC13_2") (pintype "bidirectional"))
    )
    (net (code "94") (name "unconnected-(U1A-PC14-OSC32_IN-Pad3)") (class "Default")
      (node (ref "U1") (pin "3") (pinfunction "PC14-OSC32_IN_3") (pintype "bidirectional"))
    )
    (net (code "95") (name "unconnected-(U1A-PC15-OSC32_OUT-Pad4)") (class "Default")
      (node (ref "U1") (pin "4") (pinfunction "PC15-OSC32_OUT_4") (pintype "bidirectional"))
    )
    (net (code "96") (name "unconnected-(X1-PadA8)") (class "Default")
      (node (ref "X1") (pin "A8") (pintype "passive"))
    )
    (net (code "97") (name "unconnected-(X1-PadB8)") (class "Default")
      (node (ref "X1") (pin "B8") (pintype "passive"))
    )
  )
)
